# serialdb9.net
KiCad netlist of a schematic drawn in EAGLE
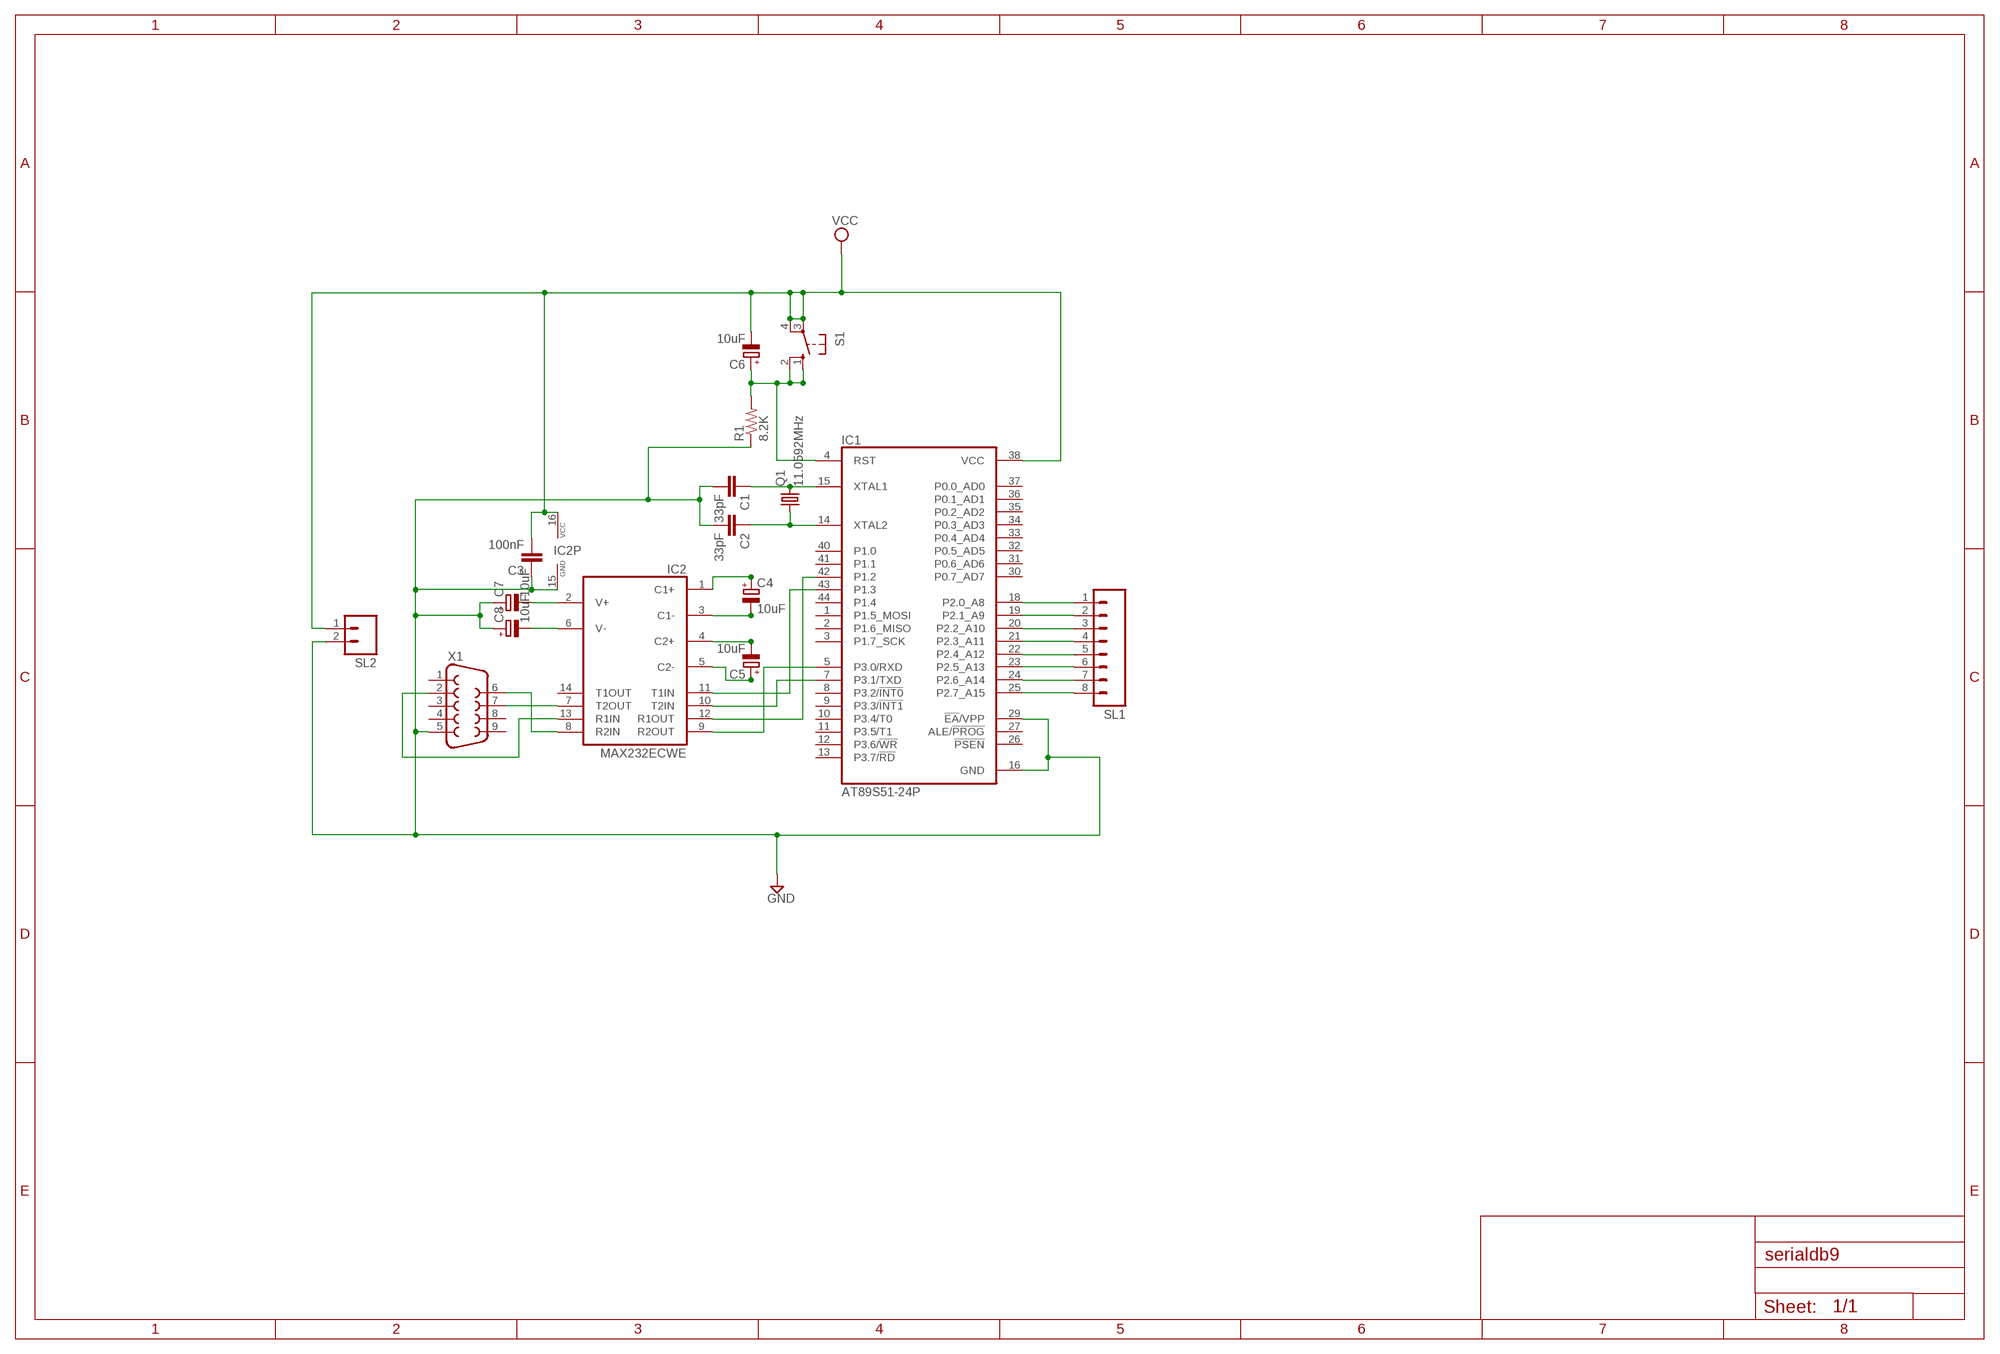
[diagram p0: schematic, sheet 1]

(export (version "E")
  (design (tool "Eeschema 10.0.6"))
  (components
    (comp (ref "C1")
      (value "33pF")
      (footprint "eagle-import:C1206K")
      (libsource (lib "eagle-import") (part "C-EUC1206K"))
    )
    (comp (ref "C2")
      (value "33pF")
      (footprint "eagle-import:C1206K")
      (libsource (lib "eagle-import") (part "C-EUC1206K"))
    )
    (comp (ref "C3")
      (value "100nF")
      (footprint "eagle-import:C1206K")
      (libsource (lib "eagle-import") (part "C-EUC1206K"))
    )
    (comp (ref "C4")
      (value "10uF")
      (footprint "eagle-import:140CLH-1010")
      (libsource (lib "eagle-import") (part "CPOL-EU140CLH-1010"))
    )
    (comp (ref "C5")
      (value "10uF")
      (footprint "eagle-import:140CLH-1010")
      (libsource (lib "eagle-import") (part "CPOL-EU140CLH-1010"))
    )
    (comp (ref "C6")
      (value "10uF")
      (footprint "eagle-import:140CLH-1010")
      (libsource (lib "eagle-import") (part "CPOL-EU140CLH-1010"))
    )
    (comp (ref "C7")
      (value "10uF")
      (footprint "eagle-import:140CLH-1010")
      (libsource (lib "eagle-import") (part "CPOL-EU140CLH-1010"))
    )
    (comp (ref "C8")
      (value "10uF")
      (footprint "eagle-import:140CLH-1010")
      (libsource (lib "eagle-import") (part "CPOL-EU140CLH-1010"))
    )
    (comp (ref "IC1")
      (value "AT89S51-24P")
      (footprint "eagle-import:TQFP44")
      (libsource (lib "eagle-import") (part "AT89S51P-24"))
    )
    (comp (ref "IC2")
      (value "MAX232ECWE")
      (footprint "eagle-import:SO16L")
      (fields (field (name "MF") "MAXIM") (field (name "MPN") "MAX232ECWE+"))
      (libsource (lib "eagle-import") (part "MAX232ECWE"))
    )
    (comp (ref "Q1")
      (value "11.0592MHz")
      (footprint "eagle-import:TC26V")
      (libsource (lib "eagle-import") (part "CRYSTALTC26V"))
    )
    (comp (ref "R1")
      (value "8.2K")
      (footprint "eagle-import:M1206")
      (libsource (lib "eagle-import") (part "R-US_M1206"))
    )
    (comp (ref "S1")
      (value "10-XX")
      (footprint "eagle-import:B3F-10XX")
      (fields (field (name "MPN") "B3F-1000"))
      (libsource (lib "eagle-import") (part "10-XX"))
    )
    (comp (ref "SL1")
      (value "MA08")
      (footprint "eagle-import:08PA")
      (libsource (lib "eagle-import") (part "MA08"))
    )
    (comp (ref "SL2")
      (value "MA02")
      (footprint "eagle-import:02PA")
      (libsource (lib "eagle-import") (part "MA02"))
    )
    (comp (ref "X1")
      (value "F09V")
      (footprint "eagle-import:F09V")
      (libsource (lib "eagle-import") (part "F09V"))
    )
  )
  (nets
    (net (code "1") (name "GND") (class "Default")
      (node (ref "C1") (pin "2") (pinfunction "2_2") (pintype "passive"))
      (node (ref "C2") (pin "2") (pinfunction "2_2") (pintype "passive"))
      (node (ref "C3") (pin "1") (pinfunction "1_1") (pintype "passive"))
      (node (ref "C7") (pin "+") (pinfunction "+_+") (pintype "passive"))
      (node (ref "C8") (pin "+") (pinfunction "+_+") (pintype "passive"))
      (node (ref "IC1") (pin "16") (pinfunction "GND_16") (pintype "power_in"))
      (node (ref "IC1") (pin "29") (pinfunction "~{EA}/VPP_29") (pintype "input"))
      (node (ref "IC2") (pin "15") (pinfunction "GND_15") (pintype "power_in"))
      (node (ref "R1") (pin "1") (pinfunction "1_1") (pintype "passive"))
      (node (ref "SL2") (pin "2") (pinfunction "2_2") (pintype "passive"))
      (node (ref "X1") (pin "5") (pinfunction "5_5") (pintype "passive"))
    )
    (net (code "2") (name "Net-(IC1A-P1.2)") (class "Default")
      (node (ref "IC1") (pin "42") (pinfunction "P1.2_42") (pintype "bidirectional"))
      (node (ref "IC2") (pin "12") (pinfunction "R1OUT_12") (pintype "output"))
    )
    (net (code "3") (name "Net-(IC1A-P1.3)") (class "Default")
      (node (ref "IC1") (pin "43") (pinfunction "P1.3_43") (pintype "bidirectional"))
      (node (ref "IC2") (pin "11") (pinfunction "T1IN_11") (pintype "input"))
    )
    (net (code "4") (name "Net-(IC1A-P2.0_A8)") (class "Default")
      (node (ref "IC1") (pin "18") (pinfunction "P2.0_A8_18") (pintype "bidirectional"))
      (node (ref "SL1") (pin "1") (pinfunction "1_1") (pintype "passive"))
    )
    (net (code "5") (name "Net-(IC1A-P2.1_A9)") (class "Default")
      (node (ref "IC1") (pin "19") (pinfunction "P2.1_A9_19") (pintype "bidirectional"))
      (node (ref "SL1") (pin "2") (pinfunction "2_2") (pintype "passive"))
    )
    (net (code "6") (name "Net-(IC1A-P2.2_A10)") (class "Default")
      (node (ref "IC1") (pin "20") (pinfunction "P2.2_A10_20") (pintype "bidirectional"))
      (node (ref "SL1") (pin "3") (pinfunction "3_3") (pintype "passive"))
    )
    (net (code "7") (name "Net-(IC1A-P2.3_A11)") (class "Default")
      (node (ref "IC1") (pin "21") (pinfunction "P2.3_A11_21") (pintype "bidirectional"))
      (node (ref "SL1") (pin "4") (pinfunction "4_4") (pintype "passive"))
    )
    (net (code "8") (name "Net-(IC1A-P2.4_A12)") (class "Default")
      (node (ref "IC1") (pin "22") (pinfunction "P2.4_A12_22") (pintype "bidirectional"))
      (node (ref "SL1") (pin "5") (pinfunction "5_5") (pintype "passive"))
    )
    (net (code "9") (name "Net-(IC1A-P2.5_A13)") (class "Default")
      (node (ref "IC1") (pin "23") (pinfunction "P2.5_A13_23") (pintype "bidirectional"))
      (node (ref "SL1") (pin "6") (pinfunction "6_6") (pintype "passive"))
    )
    (net (code "10") (name "Net-(IC1A-P2.6_A14)") (class "Default")
      (node (ref "IC1") (pin "24") (pinfunction "P2.6_A14_24") (pintype "bidirectional"))
      (node (ref "SL1") (pin "7") (pinfunction "7_7") (pintype "passive"))
    )
    (net (code "11") (name "Net-(IC1A-P2.7_A15)") (class "Default")
      (node (ref "IC1") (pin "25") (pinfunction "P2.7_A15_25") (pintype "bidirectional"))
      (node (ref "SL1") (pin "8") (pinfunction "8_8") (pintype "passive"))
    )
    (net (code "12") (name "Net-(IC1A-P3.0{slash}RXD)") (class "Default")
      (node (ref "IC1") (pin "5") (pinfunction "P3.0/RXD_5") (pintype "bidirectional"))
      (node (ref "IC2") (pin "9") (pinfunction "R2OUT_9") (pintype "output"))
    )
    (net (code "13") (name "Net-(IC1A-P3.1{slash}TXD)") (class "Default")
      (node (ref "IC1") (pin "7") (pinfunction "P3.1/TXD_7") (pintype "bidirectional"))
      (node (ref "IC2") (pin "10") (pinfunction "T2IN_10") (pintype "input"))
    )
    (net (code "14") (name "Net-(IC1A-RST)") (class "Default")
      (node (ref "C6") (pin "+") (pinfunction "+_+") (pintype "passive"))
      (node (ref "IC1") (pin "4") (pinfunction "RST_4") (pintype "input"))
      (node (ref "R1") (pin "2") (pinfunction "2_2") (pintype "passive"))
      (node (ref "S1") (pin "1") (pinfunction "S_1") (pintype "passive"))
      (node (ref "S1") (pin "2") (pinfunction "S1_2") (pintype "passive"))
    )
    (net (code "15") (name "Net-(IC1A-XTAL1)") (class "Default")
      (node (ref "C1") (pin "1") (pinfunction "1_1") (pintype "passive"))
      (node (ref "IC1") (pin "15") (pinfunction "XTAL1_15") (pintype "input"))
      (node (ref "Q1") (pin "2") (pinfunction "2_2") (pintype "passive"))
    )
    (net (code "16") (name "Net-(IC1A-XTAL2)") (class "Default")
      (node (ref "C2") (pin "1") (pinfunction "1_1") (pintype "passive"))
      (node (ref "IC1") (pin "14") (pinfunction "XTAL2_14") (pintype "input"))
      (node (ref "Q1") (pin "1") (pinfunction "1_1") (pintype "passive"))
    )
    (net (code "17") (name "Net-(IC2A-C1+)") (class "Default")
      (node (ref "C4") (pin "+") (pinfunction "+_+") (pintype "passive"))
      (node (ref "IC2") (pin "1") (pinfunction "C1+_1") (pintype "bidirectional"))
    )
    (net (code "18") (name "Net-(IC2A-C1-)") (class "Default")
      (node (ref "C4") (pin "-") (pinfunction "-_-") (pintype "passive"))
      (node (ref "IC2") (pin "3") (pinfunction "C1-_3") (pintype "bidirectional"))
    )
    (net (code "19") (name "Net-(IC2A-C2+)") (class "Default")
      (node (ref "C5") (pin "-") (pinfunction "-_-") (pintype "passive"))
      (node (ref "IC2") (pin "4") (pinfunction "C2+_4") (pintype "bidirectional"))
    )
    (net (code "20") (name "Net-(IC2A-C2-)") (class "Default")
      (node (ref "C5") (pin "+") (pinfunction "+_+") (pintype "passive"))
      (node (ref "IC2") (pin "5") (pinfunction "C2-_5") (pintype "bidirectional"))
    )
    (net (code "21") (name "Net-(IC2A-R1IN)") (class "Default")
      (node (ref "IC2") (pin "13") (pinfunction "R1IN_13") (pintype "input"))
      (node (ref "X1") (pin "2") (pinfunction "2_2") (pintype "passive"))
    )
    (net (code "22") (name "Net-(IC2A-R2IN)") (class "Default")
      (node (ref "IC2") (pin "8") (pinfunction "R2IN_8") (pintype "input"))
      (node (ref "X1") (pin "6") (pinfunction "6_6") (pintype "passive"))
    )
    (net (code "23") (name "Net-(IC2A-T2OUT)") (class "Default")
      (node (ref "IC2") (pin "7") (pinfunction "T2OUT_7") (pintype "output"))
      (node (ref "X1") (pin "7") (pinfunction "7_7") (pintype "passive"))
    )
    (net (code "24") (name "Net-(IC2A-V+)") (class "Default")
      (node (ref "C7") (pin "-") (pinfunction "-_-") (pintype "passive"))
      (node (ref "IC2") (pin "2") (pinfunction "V+_2") (pintype "bidirectional"))
    )
    (net (code "25") (name "Net-(IC2A-V-)") (class "Default")
      (node (ref "C8") (pin "-") (pinfunction "-_-") (pintype "passive"))
      (node (ref "IC2") (pin "6") (pinfunction "V-_6") (pintype "bidirectional"))
    )
    (net (code "26") (name "VCC") (class "Default")
      (node (ref "C3") (pin "2") (pinfunction "2_2") (pintype "passive"))
      (node (ref "C6") (pin "-") (pinfunction "-_-") (pintype "passive"))
      (node (ref "IC1") (pin "38") (pinfunction "VCC_38") (pintype "power_in"))
      (node (ref "IC2") (pin "16") (pinfunction "VCC_16") (pintype "power_in"))
      (node (ref "S1") (pin "3") (pinfunction "P_3") (pintype "passive"))
      (node (ref "S1") (pin "4") (pinfunction "P1_4") (pintype "passive"))
      (node (ref "SL2") (pin "1") (pinfunction "1_1") (pintype "passive"))
    )
    (net (code "27") (name "unconnected-(IC1A-ALE{slash}~{PROG}-Pad27)") (class "Default")
      (node (ref "IC1") (pin "27") (pinfunction "ALE/~{PROG}_27") (pintype "output"))
    )
    (net (code "28") (name "unconnected-(IC1A-P0.0_AD0-Pad37)") (class "Default")
      (node (ref "IC1") (pin "37") (pinfunction "P0.0_AD0_37") (pintype "bidirectional"))
    )
    (net (code "29") (name "unconnected-(IC1A-P0.1_AD1-Pad36)") (class "Default")
      (node (ref "IC1") (pin "36") (pinfunction "P0.1_AD1_36") (pintype "bidirectional"))
    )
    (net (code "30") (name "unconnected-(IC1A-P0.2_AD2-Pad35)") (class "Default")
      (node (ref "IC1") (pin "35") (pinfunction "P0.2_AD2_35") (pintype "bidirectional"))
    )
    (net (code "31") (name "unconnected-(IC1A-P0.3_AD3-Pad34)") (class "Default")
      (node (ref "IC1") (pin "34") (pinfunction "P0.3_AD3_34") (pintype "bidirectional"))
    )
    (net (code "32") (name "unconnected-(IC1A-P0.4_AD4-Pad33)") (class "Default")
      (node (ref "IC1") (pin "33") (pinfunction "P0.4_AD4_33") (pintype "bidirectional"))
    )
    (net (code "33") (name "unconnected-(IC1A-P0.5_AD5-Pad32)") (class "Default")
      (node (ref "IC1") (pin "32") (pinfunction "P0.5_AD5_32") (pintype "bidirectional"))
    )
    (net (code "34") (name "unconnected-(IC1A-P0.6_AD6-Pad31)") (class "Default")
      (node (ref "IC1") (pin "31") (pinfunction "P0.6_AD6_31") (pintype "bidirectional"))
    )
    (net (code "35") (name "unconnected-(IC1A-P0.7_AD7-Pad30)") (class "Default")
      (node (ref "IC1") (pin "30") (pinfunction "P0.7_AD7_30") (pintype "bidirectional"))
    )
    (net (code "36") (name "unconnected-(IC1A-P1.0-Pad40)") (class "Default")
      (node (ref "IC1") (pin "40") (pinfunction "P1.0_40") (pintype "bidirectional"))
    )
    (net (code "37") (name "unconnected-(IC1A-P1.1-Pad41)") (class "Default")
      (node (ref "IC1") (pin "41") (pinfunction "P1.1_41") (pintype "bidirectional"))
    )
    (net (code "38") (name "unconnected-(IC1A-P1.4-Pad44)") (class "Default")
      (node (ref "IC1") (pin "44") (pinfunction "P1.4_44") (pintype "bidirectional"))
    )
    (net (code "39") (name "unconnected-(IC1A-P1.5_MOSI-Pad1)") (class "Default")
      (node (ref "IC1") (pin "1") (pinfunction "P1.5_MOSI_1") (pintype "bidirectional"))
    )
    (net (code "40") (name "unconnected-(IC1A-P1.6_MISO-Pad2)") (class "Default")
      (node (ref "IC1") (pin "2") (pinfunction "P1.6_MISO_2") (pintype "bidirectional"))
    )
    (net (code "41") (name "unconnected-(IC1A-P1.7_SCK-Pad3)") (class "Default")
      (node (ref "IC1") (pin "3") (pinfunction "P1.7_SCK_3") (pintype "bidirectional"))
    )
    (net (code "42") (name "unconnected-(IC1A-P3.2{slash}~{INT0}-Pad8)") (class "Default")
      (node (ref "IC1") (pin "8") (pinfunction "P3.2/~{INT0}_8") (pintype "bidirectional"))
    )
    (net (code "43") (name "unconnected-(IC1A-P3.3{slash}~{INT1}-Pad9)") (class "Default")
      (node (ref "IC1") (pin "9") (pinfunction "P3.3/~{INT1}_9") (pintype "bidirectional"))
    )
    (net (code "44") (name "unconnected-(IC1A-P3.4{slash}T0-Pad10)") (class "Default")
      (node (ref "IC1") (pin "10") (pinfunction "P3.4/T0_10") (pintype "bidirectional"))
    )
    (net (code "45") (name "unconnected-(IC1A-P3.5{slash}T1-Pad11)") (class "Default")
      (node (ref "IC1") (pin "11") (pinfunction "P3.5/T1_11") (pintype "bidirectional"))
    )
    (net (code "46") (name "unconnected-(IC1A-P3.6{slash}~{WR}-Pad12)") (class "Default")
      (node (ref "IC1") (pin "12") (pinfunction "P3.6/~{WR}_12") (pintype "bidirectional"))
    )
    (net (code "47") (name "unconnected-(IC1A-P3.7{slash}~{RD}-Pad13)") (class "Default")
      (node (ref "IC1") (pin "13") (pinfunction "P3.7/~{RD}_13") (pintype "bidirectional"))
    )
    (net (code "48") (name "unconnected-(IC1A-~{PSEN}-Pad26)") (class "Default")
      (node (ref "IC1") (pin "26") (pinfunction "~{PSEN}_26") (pintype "output"))
    )
    (net (code "49") (name "unconnected-(IC2A-T1OUT-Pad14)") (class "Default")
      (node (ref "IC2") (pin "14") (pinfunction "T1OUT_14") (pintype "output"))
    )
    (net (code "50") (name "unconnected-(X1-Pad1)") (class "Default")
      (node (ref "X1") (pin "1") (pinfunction "1_1") (pintype "passive"))
    )
    (net (code "51") (name "unconnected-(X1-Pad3)") (class "Default")
      (node (ref "X1") (pin "3") (pinfunction "3_3") (pintype "passive"))
    )
    (net (code "52") (name "unconnected-(X1-Pad4)") (class "Default")
      (node (ref "X1") (pin "4") (pinfunction "4_4") (pintype "passive"))
    )
    (net (code "53") (name "unconnected-(X1-Pad8)") (class "Default")
      (node (ref "X1") (pin "8") (pinfunction "8_8") (pintype "passive"))
    )
    (net (code "54") (name "unconnected-(X1-Pad9)") (class "Default")
      (node (ref "X1") (pin "9") (pinfunction "9_9") (pintype "passive"))
    )
  )
)
